# ardu.net
KiCad netlist of a schematic drawn in EAGLE
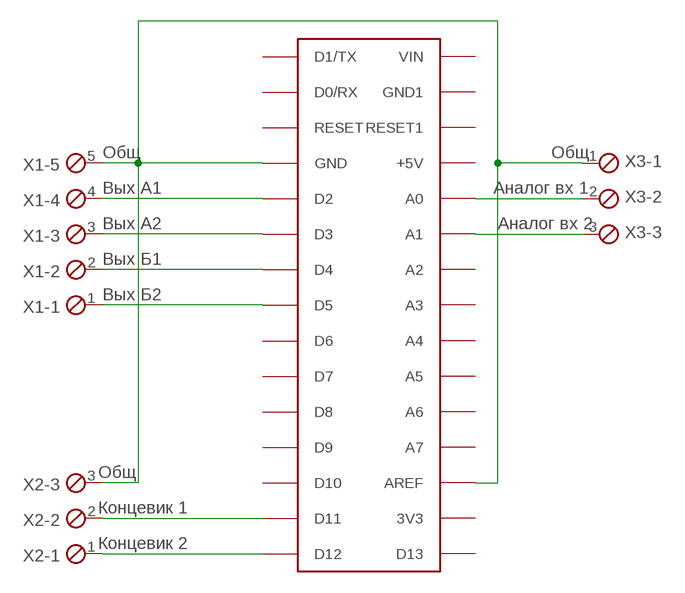
[diagram p0: schematic, sheet 1]

(export (version "E")
  (design (tool "Eeschema 10.0.6"))
  (components
    (comp (ref "U$1")
      (value "ARDUINONANO")
      (footprint "eagle-import:PDIP-32")
      (libsource (lib "eagle-import") (part "ARDUINONANO"))
    )
    (comp (ref "X1")
      (value "MPT5")
      (footprint "eagle-import:5POL254")
      (libsource (lib "eagle-import") (part "MPT5"))
    )
    (comp (ref "X2")
      (value "MPT3")
      (footprint "eagle-import:3POL254")
      (libsource (lib "eagle-import") (part "MPT3"))
    )
    (comp (ref "X3")
      (value "MPT3")
      (footprint "eagle-import:3POL254")
      (libsource (lib "eagle-import") (part "MPT3"))
    )
  )
  (nets
    (net (code "1") (name "Net-(U$1-PadD5)") (class "Default")
      (node (ref "U$1") (pin "D5") (pinfunction "D5_D5") (pintype "bidirectional"))
      (node (ref "X1") (pin "1") (pinfunction "1_1") (pintype "passive"))
    )
    (net (code "2") (name "Net-(U$1-PadD12)") (class "Default")
      (node (ref "U$1") (pin "D12") (pinfunction "D12_D12") (pintype "bidirectional"))
      (node (ref "X2") (pin "1") (pinfunction "1_1") (pintype "passive"))
    )
    (net (code "3") (name "Net-(X1B-1)") (class "Default")
      (node (ref "U$1") (pin "D4") (pinfunction "D4_D4") (pintype "bidirectional"))
      (node (ref "X1") (pin "2") (pinfunction "1_2") (pintype "passive"))
    )
    (net (code "4") (name "Net-(X1C-1)") (class "Default")
      (node (ref "U$1") (pin "D3") (pinfunction "D3_D3") (pintype "bidirectional"))
      (node (ref "X1") (pin "3") (pinfunction "1_3") (pintype "passive"))
    )
    (net (code "5") (name "Net-(X1D-1)") (class "Default")
      (node (ref "U$1") (pin "D2") (pinfunction "D2_D2") (pintype "bidirectional"))
      (node (ref "X1") (pin "4") (pinfunction "1_4") (pintype "passive"))
    )
    (net (code "6") (name "Net-(X1E-1)") (class "Default")
      (node (ref "U$1") (pin "AREF") (pinfunction "AREF_AREF") (pintype "bidirectional"))
      (node (ref "U$1") (pin "GND") (pinfunction "GND_GND") (pintype "bidirectional"))
      (node (ref "X1") (pin "5") (pinfunction "1_5") (pintype "passive"))
      (node (ref "X2") (pin "3") (pinfunction "1_3") (pintype "passive"))
      (node (ref "X3") (pin "1") (pinfunction "1_1") (pintype "passive"))
    )
    (net (code "7") (name "Net-(X2B-1)") (class "Default")
      (node (ref "U$1") (pin "D11") (pinfunction "D11_D11") (pintype "bidirectional"))
      (node (ref "X2") (pin "2") (pinfunction "1_2") (pintype "passive"))
    )
    (net (code "8") (name "Net-(X3B-1)") (class "Default")
      (node (ref "U$1") (pin "A0") (pinfunction "A0_A0") (pintype "bidirectional"))
      (node (ref "X3") (pin "2") (pinfunction "1_2") (pintype "passive"))
    )
    (net (code "9") (name "Net-(X3C-1)") (class "Default")
      (node (ref "U$1") (pin "A1") (pinfunction "A1_A1") (pintype "bidirectional"))
      (node (ref "X3") (pin "3") (pinfunction "1_3") (pintype "passive"))
    )
    (net (code "10") (name "unconnected-(U$1-Pad+5V)") (class "Default")
      (node (ref "U$1") (pin "+5V") (pinfunction "+5V_+5V") (pintype "bidirectional"))
    )
    (net (code "11") (name "unconnected-(U$1-Pad3V3)") (class "Default")
      (node (ref "U$1") (pin "3V3") (pinfunction "3V3_3V3") (pintype "bidirectional"))
    )
    (net (code "12") (name "unconnected-(U$1-PadA2)") (class "Default")
      (node (ref "U$1") (pin "A2") (pinfunction "A2_A2") (pintype "bidirectional"))
    )
    (net (code "13") (name "unconnected-(U$1-PadA3)") (class "Default")
      (node (ref "U$1") (pin "A3") (pinfunction "A3_A3") (pintype "bidirectional"))
    )
    (net (code "14") (name "unconnected-(U$1-PadA4)") (class "Default")
      (node (ref "U$1") (pin "A4") (pinfunction "A4_A4") (pintype "bidirectional"))
    )
    (net (code "15") (name "unconnected-(U$1-PadA5)") (class "Default")
      (node (ref "U$1") (pin "A5") (pinfunction "A5_A5") (pintype "bidirectional"))
    )
    (net (code "16") (name "unconnected-(U$1-PadA6)") (class "Default")
      (node (ref "U$1") (pin "A6") (pinfunction "A6_A6") (pintype "bidirectional"))
    )
    (net (code "17") (name "unconnected-(U$1-PadA7)") (class "Default")
      (node (ref "U$1") (pin "A7") (pinfunction "A7_A7") (pintype "bidirectional"))
    )
    (net (code "18") (name "unconnected-(U$1-PadD0{slash}RX)") (class "Default")
      (node (ref "U$1") (pin "D0/RX") (pinfunction "D0/RX_D0/RX") (pintype "bidirectional"))
    )
    (net (code "19") (name "unconnected-(U$1-PadD1{slash}TX)") (class "Default")
      (node (ref "U$1") (pin "D1/TX") (pinfunction "D1/TX_D1/TX") (pintype "bidirectional"))
    )
    (net (code "20") (name "unconnected-(U$1-PadD6)") (class "Default")
      (node (ref "U$1") (pin "D6") (pinfunction "D6_D6") (pintype "bidirectional"))
    )
    (net (code "21") (name "unconnected-(U$1-PadD7)") (class "Default")
      (node (ref "U$1") (pin "D7") (pinfunction "D7_D7") (pintype "bidirectional"))
    )
    (net (code "22") (name "unconnected-(U$1-PadD8)") (class "Default")
      (node (ref "U$1") (pin "D8") (pinfunction "D8_D8") (pintype "bidirectional"))
    )
    (net (code "23") (name "unconnected-(U$1-PadD9)") (class "Default")
      (node (ref "U$1") (pin "D9") (pinfunction "D9_D9") (pintype "bidirectional"))
    )
    (net (code "24") (name "unconnected-(U$1-PadD10)") (class "Default")
      (node (ref "U$1") (pin "D10") (pinfunction "D10_D10") (pintype "bidirectional"))
    )
    (net (code "25") (name "unconnected-(U$1-PadD13)") (class "Default")
      (node (ref "U$1") (pin "D13") (pinfunction "D13_D13") (pintype "bidirectional"))
    )
    (net (code "26") (name "unconnected-(U$1-PadGND1)") (class "Default")
      (node (ref "U$1") (pin "GND1") (pinfunction "GND1_GND1") (pintype "bidirectional"))
    )
    (net (code "27") (name "unconnected-(U$1-PadRESET)") (class "Default")
      (node (ref "U$1") (pin "RESET") (pinfunction "RESET_RESET") (pintype "bidirectional"))
    )
    (net (code "28") (name "unconnected-(U$1-PadRESET1)") (class "Default")
      (node (ref "U$1") (pin "RESET1") (pinfunction "RESET1_RESET1") (pintype "bidirectional"))
    )
    (net (code "29") (name "unconnected-(U$1-PadVIN)") (class "Default")
      (node (ref "U$1") (pin "VIN") (pinfunction "VIN_VIN") (pintype "bidirectional"))
    )
  )
)
